# VoltageSourcePCBLT6000.net
KiCad netlist of a schematic drawn in EAGLE
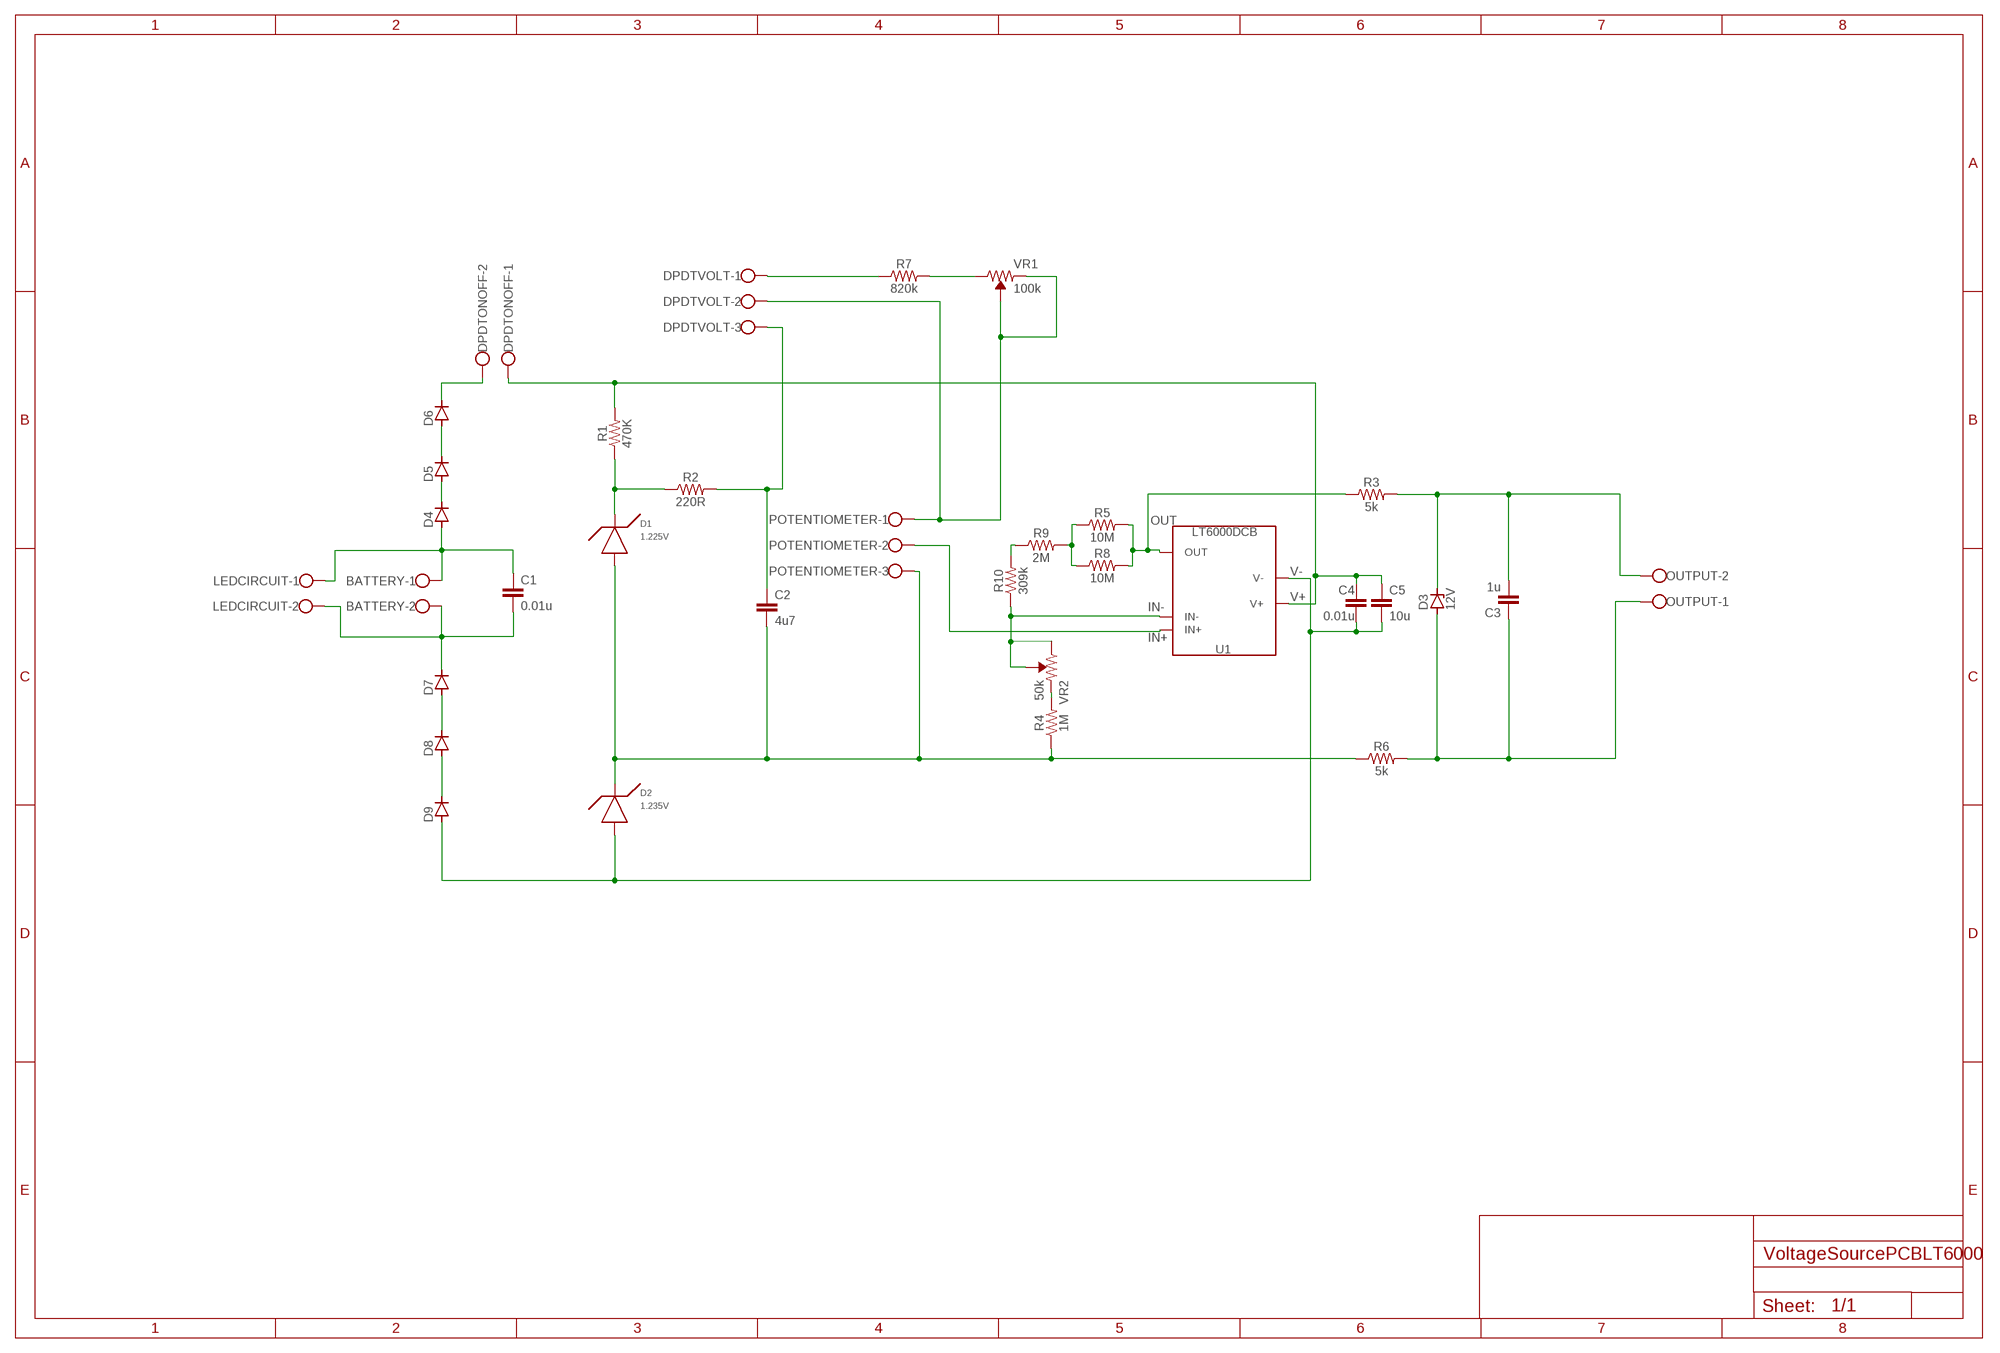
[diagram p0: schematic, sheet 1]

(export (version "E")
  (design (tool "Eeschema 10.0.6"))
  (components
    (comp (ref "BATTERY")
      (value "W237-102")
      (footprint "eagle-import:W237-102")
      (fields (field (name "MPN") "237-102"))
      (libsource (lib "eagle-import") (part "W237-102"))
    )
    (comp (ref "C1")
      (value "0.01u")
      (footprint "eagle-import:C5B2.5")
      (libsource (lib "eagle-import") (part "C5/2.5"))
    )
    (comp (ref "C2")
      (value "4u7")
      (footprint "eagle-import:C22.5B11")
      (libsource (lib "eagle-import") (part "C22/11"))
    )
    (comp (ref "C3")
      (value "1u")
      (footprint "eagle-import:C150-072X183")
      (libsource (lib "eagle-import") (part "C-EU150-072X183"))
    )
    (comp (ref "C4")
      (value "0.01u")
      (footprint "eagle-import:C5B2.5")
      (libsource (lib "eagle-import") (part "C5/2.5"))
    )
    (comp (ref "C5")
      (value "10u")
      (footprint "eagle-import:C5B2.5")
      (libsource (lib "eagle-import") (part "C5/2.5"))
    )
    (comp (ref "D1")
      (value "1.225V")
      (footprint "eagle-import:LT1004CZ")
      (libsource (lib "eagle-import") (part "LT1004CZ1.225V"))
    )
    (comp (ref "D2")
      (value "1.235V")
      (footprint "eagle-import:LT1004CZ")
      (libsource (lib "eagle-import") (part "LT1004CZ1.235V"))
    )
    (comp (ref "D3")
      (value "12V")
      (footprint "eagle-import:C1702-15")
      (libsource (lib "eagle-import") (part "ZENER-DIODEC1702-15"))
    )
    (comp (ref "D4")
      (value "D-SOD123")
      (footprint "eagle-import:SOD123")
      (libsource (lib "eagle-import") (part "D-SOD123"))
    )
    (comp (ref "D5")
      (value "D-SOD123")
      (footprint "eagle-import:SOD123")
      (libsource (lib "eagle-import") (part "D-SOD123"))
    )
    (comp (ref "D6")
      (value "D-SOD123")
      (footprint "eagle-import:SOD123")
      (libsource (lib "eagle-import") (part "D-SOD123"))
    )
    (comp (ref "D7")
      (value "D-SOD123")
      (footprint "eagle-import:SOD123")
      (libsource (lib "eagle-import") (part "D-SOD123"))
    )
    (comp (ref "D8")
      (value "D-SOD123")
      (footprint "eagle-import:SOD123")
      (libsource (lib "eagle-import") (part "D-SOD123"))
    )
    (comp (ref "D9")
      (value "D-SOD123")
      (footprint "eagle-import:SOD123")
      (libsource (lib "eagle-import") (part "D-SOD123"))
    )
    (comp (ref "DPDTONOFF")
      (value "W237-102")
      (footprint "eagle-import:W237-102")
      (fields (field (name "MPN") "237-102"))
      (libsource (lib "eagle-import") (part "W237-102"))
    )
    (comp (ref "DPDTVOLT")
      (value "W237-103")
      (footprint "eagle-import:W237-103")
      (fields (field (name "MPN") "237-103"))
      (libsource (lib "eagle-import") (part "W237-103"))
    )
    (comp (ref "LEDCIRCUIT")
      (value "W237-102")
      (footprint "eagle-import:W237-102")
      (fields (field (name "MPN") "237-102"))
      (libsource (lib "eagle-import") (part "W237-102"))
    )
    (comp (ref "OUTPUT")
      (value "W237-102")
      (footprint "eagle-import:W237-102")
      (fields (field (name "MPN") "237-102"))
      (libsource (lib "eagle-import") (part "W237-102"))
    )
    (comp (ref "POTENTIOMETER")
      (value "W237-103")
      (footprint "eagle-import:W237-103")
      (fields (field (name "MPN") "237-103"))
      (libsource (lib "eagle-import") (part "W237-103"))
    )
    (comp (ref "R1")
      (value "470K")
      (footprint "eagle-import:0805")
      (libsource (lib "eagle-import") (part "RESISTOR0805"))
    )
    (comp (ref "R2")
      (value "220R")
      (footprint "eagle-import:0805")
      (libsource (lib "eagle-import") (part "RESISTOR0805"))
    )
    (comp (ref "R3")
      (value "5k")
      (footprint "eagle-import:0805")
      (libsource (lib "eagle-import") (part "RESISTOR0805"))
    )
    (comp (ref "R4")
      (value "1M")
      (footprint "eagle-import:0805")
      (libsource (lib "eagle-import") (part "RESISTOR0805"))
    )
    (comp (ref "R5")
      (value "10M")
      (footprint "eagle-import:0805")
      (libsource (lib "eagle-import") (part "RESISTOR0805"))
    )
    (comp (ref "R6")
      (value "5k")
      (footprint "eagle-import:0805")
      (libsource (lib "eagle-import") (part "RESISTOR0805"))
    )
    (comp (ref "R7")
      (value "820k")
      (footprint "eagle-import:0805")
      (libsource (lib "eagle-import") (part "RESISTOR0805"))
    )
    (comp (ref "R8")
      (value "10M")
      (footprint "eagle-import:0805")
      (libsource (lib "eagle-import") (part "RESISTOR0805"))
    )
    (comp (ref "R9")
      (value "2M")
      (footprint "eagle-import:0805")
      (libsource (lib "eagle-import") (part "RESISTOR0805"))
    )
    (comp (ref "R10")
      (value "309k")
      (footprint "eagle-import:0805")
      (libsource (lib "eagle-import") (part "RESISTOR0805"))
    )
    (comp (ref "U1")
      (value "LT6000DCB")
      (footprint "eagle-import:LT6000")
      (libsource (lib "eagle-import") (part "LT6000DCB"))
    )
    (comp (ref "VR1")
      (value "100k")
      (footprint "eagle-import:TRIMPOT-SMD-TC33X")
      (libsource (lib "eagle-import") (part "TRIMPOT-SMD-3MM-OPEN-1/10W-25%"))
    )
    (comp (ref "VR2")
      (value "50k")
      (footprint "eagle-import:TRIMPOT-SMD-TC33X")
      (libsource (lib "eagle-import") (part "TRIMPOT-SMD-3MM-OPEN-1/10W-25%"))
    )
  )
  (nets
    (net (code "1") (name "/IN+") (class "Default")
      (node (ref "POTENTIOMETER") (pin "2") (pinfunction "KL_2") (pintype "passive"))
      (node (ref "U1") (pin "3") (pinfunction "IN+_3") (pintype "input"))
    )
    (net (code "2") (name "/IN-") (class "Default")
      (node (ref "R10") (pin "1") (pinfunction "1_1") (pintype "passive"))
      (node (ref "U1") (pin "2") (pinfunction "IN-_2") (pintype "input"))
      (node (ref "VR2") (pin "1") (pinfunction "CW_1") (pintype "passive"))
      (node (ref "VR2") (pin "2") (pinfunction "WIPER_2") (pintype "passive"))
    )
    (net (code "3") (name "/OUT") (class "Default")
      (node (ref "R3") (pin "1") (pinfunction "1_1") (pintype "passive"))
      (node (ref "R5") (pin "2") (pinfunction "2_2") (pintype "passive"))
      (node (ref "R8") (pin "2") (pinfunction "2_2") (pintype "passive"))
      (node (ref "U1") (pin "4") (pinfunction "OUT_4") (pintype "output"))
    )
    (net (code "4") (name "/V+") (class "Default")
      (node (ref "C4") (pin "1") (pinfunction "1_1") (pintype "passive"))
      (node (ref "C5") (pin "1") (pinfunction "1_1") (pintype "passive"))
      (node (ref "DPDTONOFF") (pin "1") (pinfunction "KL_1") (pintype "passive"))
      (node (ref "R1") (pin "2") (pinfunction "2_2") (pintype "passive"))
      (node (ref "U1") (pin "6") (pinfunction "V+_6") (pintype "power_in"))
    )
    (net (code "5") (name "/V-") (class "Default")
      (node (ref "C4") (pin "2") (pinfunction "2_2") (pintype "passive"))
      (node (ref "C5") (pin "2") (pinfunction "2_2") (pintype "passive"))
      (node (ref "D2") (pin "ANODE") (pinfunction "ANODE_ANODE") (pintype "bidirectional"))
      (node (ref "D9") (pin "2") (pinfunction "A_2") (pintype "passive"))
      (node (ref "U1") (pin "5") (pinfunction "V-_5") (pintype "power_in"))
      (node (ref "U1") (pin "7") (pinfunction "V-_7") (pintype "power_in"))
    )
    (net (code "6") (name "Net-(BATTERYA-KL)") (class "Default")
      (node (ref "BATTERY") (pin "1") (pinfunction "KL_1") (pintype "passive"))
      (node (ref "C1") (pin "1") (pinfunction "1_1") (pintype "passive"))
      (node (ref "D4") (pin "2") (pinfunction "A_2") (pintype "passive"))
      (node (ref "LEDCIRCUIT") (pin "1") (pinfunction "KL_1") (pintype "passive"))
    )
    (net (code "7") (name "Net-(BATTERYB-KL)") (class "Default")
      (node (ref "BATTERY") (pin "2") (pinfunction "KL_2") (pintype "passive"))
      (node (ref "C1") (pin "2") (pinfunction "2_2") (pintype "passive"))
      (node (ref "D7") (pin "1") (pinfunction "C_1") (pintype "passive"))
      (node (ref "LEDCIRCUIT") (pin "2") (pinfunction "KL_2") (pintype "passive"))
    )
    (net (code "8") (name "Net-(D1-PadCATHODE)") (class "Default")
      (node (ref "D1") (pin "CATHODE") (pinfunction "CATHODE_CATHODE") (pintype "bidirectional"))
      (node (ref "R1") (pin "1") (pinfunction "1_1") (pintype "passive"))
      (node (ref "R2") (pin "1") (pinfunction "1_1") (pintype "passive"))
    )
    (net (code "9") (name "Net-(D4-C)") (class "Default")
      (node (ref "D4") (pin "1") (pinfunction "C_1") (pintype "passive"))
      (node (ref "D5") (pin "2") (pinfunction "A_2") (pintype "passive"))
    )
    (net (code "10") (name "Net-(D5-C)") (class "Default")
      (node (ref "D5") (pin "1") (pinfunction "C_1") (pintype "passive"))
      (node (ref "D6") (pin "2") (pinfunction "A_2") (pintype "passive"))
    )
    (net (code "11") (name "Net-(D6-C)") (class "Default")
      (node (ref "D6") (pin "1") (pinfunction "C_1") (pintype "passive"))
      (node (ref "DPDTONOFF") (pin "2") (pinfunction "KL_2") (pintype "passive"))
    )
    (net (code "12") (name "Net-(D7-A)") (class "Default")
      (node (ref "D7") (pin "2") (pinfunction "A_2") (pintype "passive"))
      (node (ref "D8") (pin "1") (pinfunction "C_1") (pintype "passive"))
    )
    (net (code "13") (name "Net-(D8-A)") (class "Default")
      (node (ref "D8") (pin "2") (pinfunction "A_2") (pintype "passive"))
      (node (ref "D9") (pin "1") (pinfunction "C_1") (pintype "passive"))
    )
    (net (code "14") (name "Net-(DPDTVOLTA-KL)") (class "Default")
      (node (ref "DPDTVOLT") (pin "1") (pinfunction "KL_1") (pintype "passive"))
      (node (ref "R7") (pin "1") (pinfunction "1_1") (pintype "passive"))
    )
    (net (code "15") (name "Net-(DPDTVOLTB-KL)") (class "Default")
      (node (ref "DPDTVOLT") (pin "2") (pinfunction "KL_2") (pintype "passive"))
      (node (ref "POTENTIOMETER") (pin "1") (pinfunction "KL_1") (pintype "passive"))
      (node (ref "VR1") (pin "2") (pinfunction "WIPER_2") (pintype "passive"))
      (node (ref "VR1") (pin "3") (pinfunction "CCW_3") (pintype "passive"))
    )
    (net (code "16") (name "Net-(DPDTVOLTC-KL)") (class "Default")
      (node (ref "C2") (pin "1") (pinfunction "1_1") (pintype "passive"))
      (node (ref "DPDTVOLT") (pin "3") (pinfunction "KL_3") (pintype "passive"))
      (node (ref "R2") (pin "2") (pinfunction "2_2") (pintype "passive"))
    )
    (net (code "17") (name "Net-(OUTPUTA-KL)") (class "Default")
      (node (ref "C3") (pin "1") (pinfunction "1_1") (pintype "passive"))
      (node (ref "D3") (pin "A") (pinfunction "A_A") (pintype "passive"))
      (node (ref "OUTPUT") (pin "1") (pinfunction "KL_1") (pintype "passive"))
      (node (ref "R6") (pin "2") (pinfunction "2_2") (pintype "passive"))
    )
    (net (code "18") (name "Net-(OUTPUTB-KL)") (class "Default")
      (node (ref "C3") (pin "2") (pinfunction "2_2") (pintype "passive"))
      (node (ref "D3") (pin "C") (pinfunction "C_C") (pintype "passive"))
      (node (ref "OUTPUT") (pin "2") (pinfunction "KL_2") (pintype "passive"))
      (node (ref "R3") (pin "2") (pinfunction "2_2") (pintype "passive"))
    )
    (net (code "19") (name "Net-(POTENTIOMETERC-KL)") (class "Default")
      (node (ref "C2") (pin "2") (pinfunction "2_2") (pintype "passive"))
      (node (ref "D1") (pin "ANODE") (pinfunction "ANODE_ANODE") (pintype "bidirectional"))
      (node (ref "D2") (pin "CATHODE") (pinfunction "CATHODE_CATHODE") (pintype "bidirectional"))
      (node (ref "POTENTIOMETER") (pin "3") (pinfunction "KL_3") (pintype "passive"))
      (node (ref "R4") (pin "1") (pinfunction "1_1") (pintype "passive"))
      (node (ref "R6") (pin "1") (pinfunction "1_1") (pintype "passive"))
    )
    (net (code "20") (name "Net-(R5-Pad1)") (class "Default")
      (node (ref "R5") (pin "1") (pinfunction "1_1") (pintype "passive"))
      (node (ref "R8") (pin "1") (pinfunction "1_1") (pintype "passive"))
      (node (ref "R9") (pin "2") (pinfunction "2_2") (pintype "passive"))
    )
    (net (code "21") (name "Net-(R10-Pad2)") (class "Default")
      (node (ref "R10") (pin "2") (pinfunction "2_2") (pintype "passive"))
      (node (ref "R9") (pin "1") (pinfunction "1_1") (pintype "passive"))
    )
    (net (code "22") (name "Net-(VR1-CW)") (class "Default")
      (node (ref "R7") (pin "2") (pinfunction "2_2") (pintype "passive"))
      (node (ref "VR1") (pin "1") (pinfunction "CW_1") (pintype "passive"))
    )
    (net (code "23") (name "Net-(VR2-CCW)") (class "Default")
      (node (ref "R4") (pin "2") (pinfunction "2_2") (pintype "passive"))
      (node (ref "VR2") (pin "3") (pinfunction "CCW_3") (pintype "passive"))
    )
  )
)
